# Sheet1.net
KiCad netlist of a schematic drawn in Altium Designer
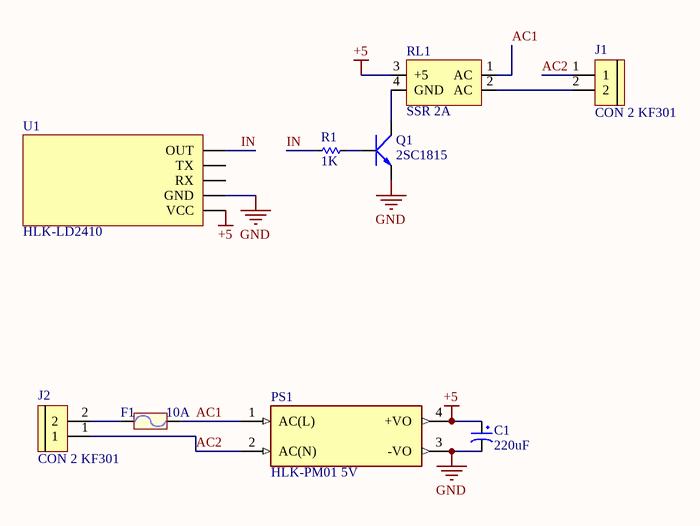
[diagram p0: Sheet1.SchDoc]

(export (version "E")
  (design (tool "Eeschema 10.0.6"))
  (components
    (comp (ref "C1")
      (value "220uF")
      (footprint "Tu hoa 5mm")
      (description "Cắm")
      (libsource (lib "Altium_Lib_by_KhueNguyenCreator") (part "Tu Hoa 220uF 16V 6x11"))
    )
    (comp (ref "F1")
      (value "10A")
      (footprint "Fuse vertical")
      (description "Fuse")
      (fields (field (name "DESIGNED BY") "VanDungEvn"))
      (libsource (lib "iuh-thuc-hanh") (part "Fuse"))
    )
    (comp (ref "J1")
      (value "CON 2 KF301")
      (footprint "Con 2 KF301 5.08")
      (description "Cắm")
      (libsource (lib "") (part "CON 2 KF301_1"))
    )
    (comp (ref "J2")
      (value "CON 2 KF301")
      (footprint "Con 2 KF301 5.08")
      (description "Cắm")
      (libsource (lib "Altium_Lib_by_KhueNguyenCreator") (part "CON 2 KF301"))
    )
    (comp (ref "PS1")
      (value "HLK-PM01 5V")
      (footprint "CONV_HLK-PM01")
      (description "220VAC to 5V 3W")
      (fields (field (name "MF") "Hi-link") (field (name "MP") "HLK-20M12"))
      (libsource (lib "iuh-thuc-hanh") (part "CONV HLK-PM01"))
    )
    (comp (ref "Q1")
      (value "2SC1815")
      (footprint "TO92-123")
      (description "NPN 600mW, ECB")
      (libsource (lib "LIBRARY1") (part "2SC1815"))
    )
    (comp (ref "R1") (value "1K") (footprint "RES-1/4W") (libsource (lib "iuh-thuc-hanh") (part "Res")))
    (comp (ref "RL1")
      (value "SSR 2A")
      (footprint "G3MB-202P")
      (description "SSR 5V 2A")
      (libsource (lib "iuh-thuc-hanh") (part "SSR G3MB-202P"))
    )
    (comp (ref "U1")
      (value "HLK-LD2410")
      (footprint "HLK-LD2410")
      (description "HLK-LD2410B-P Cam bien hien dien")
      (libsource (lib "iuh-thuc-hanh") (part "HLK-LD2410"))
    )
  )
  (nets
    (net (code "1") (name "+5") (class "Default")
      (node (ref "C1") (pin "1") (pinfunction "1_1") (pintype "passive"))
      (node (ref "PS1") (pin "4") (pinfunction "+VO_4") (pintype "output"))
      (node (ref "RL1") (pin "3") (pinfunction "+5_3") (pintype "passive"))
      (node (ref "U1") (pin "5") (pinfunction "VCC_5") (pintype "passive"))
    )
    (net (code "2") (name "/AC1") (class "Default")
      (node (ref "F1") (pin "2") (pinfunction "2_2") (pintype "passive"))
      (node (ref "PS1") (pin "1") (pinfunction "AC(L)_1") (pintype "input"))
      (node (ref "RL1") (pin "1") (pinfunction "AC_1") (pintype "passive"))
    )
    (net (code "3") (name "/AC2") (class "Default")
      (node (ref "J1") (pin "1") (pinfunction "1_1") (pintype "passive"))
      (node (ref "J2") (pin "1") (pinfunction "1_1") (pintype "passive"))
      (node (ref "PS1") (pin "2") (pinfunction "AC(N)_2") (pintype "input"))
    )
    (net (code "4") (name "/IN") (class "Default")
      (node (ref "R1") (pin "2") (pinfunction "2_2") (pintype "passive"))
      (node (ref "U1") (pin "1") (pinfunction "OUT_1") (pintype "passive"))
    )
    (net (code "5") (name "GND") (class "Default")
      (node (ref "C1") (pin "2") (pinfunction "2_2") (pintype "passive"))
      (node (ref "PS1") (pin "3") (pinfunction "-VO_3") (pintype "output"))
      (node (ref "Q1") (pin "1") (pinfunction "E_1") (pintype "passive"))
      (node (ref "U1") (pin "4") (pinfunction "GND_4") (pintype "passive"))
    )
    (net (code "6") (name "Net-(F1-Pad1)") (class "Default")
      (node (ref "F1") (pin "1") (pinfunction "1_1") (pintype "passive"))
      (node (ref "J2") (pin "2") (pinfunction "2_2") (pintype "passive"))
    )
    (net (code "7") (name "Net-(J1-Pad2)") (class "Default")
      (node (ref "J1") (pin "2") (pinfunction "2_2") (pintype "passive"))
      (node (ref "RL1") (pin "2") (pinfunction "AC_2") (pintype "passive"))
    )
    (net (code "8") (name "Net-(Q1-B)") (class "Default")
      (node (ref "Q1") (pin "3") (pinfunction "B_3") (pintype "passive"))
      (node (ref "R1") (pin "1") (pinfunction "1_1") (pintype "passive"))
    )
    (net (code "9") (name "Net-(Q1-C)") (class "Default")
      (node (ref "Q1") (pin "2") (pinfunction "C_2") (pintype "passive"))
      (node (ref "RL1") (pin "4") (pinfunction "GND_4") (pintype "passive"))
    )
    (net (code "10") (name "unconnected-(U1-RX-Pad3)") (class "Default")
      (node (ref "U1") (pin "3") (pinfunction "RX_3") (pintype "passive"))
    )
    (net (code "11") (name "unconnected-(U1-TX-Pad2)") (class "Default")
      (node (ref "U1") (pin "2") (pinfunction "TX_2") (pintype "passive"))
    )
  )
)
